# esp_sense.net
KiCad netlist of a schematic drawn in EAGLE
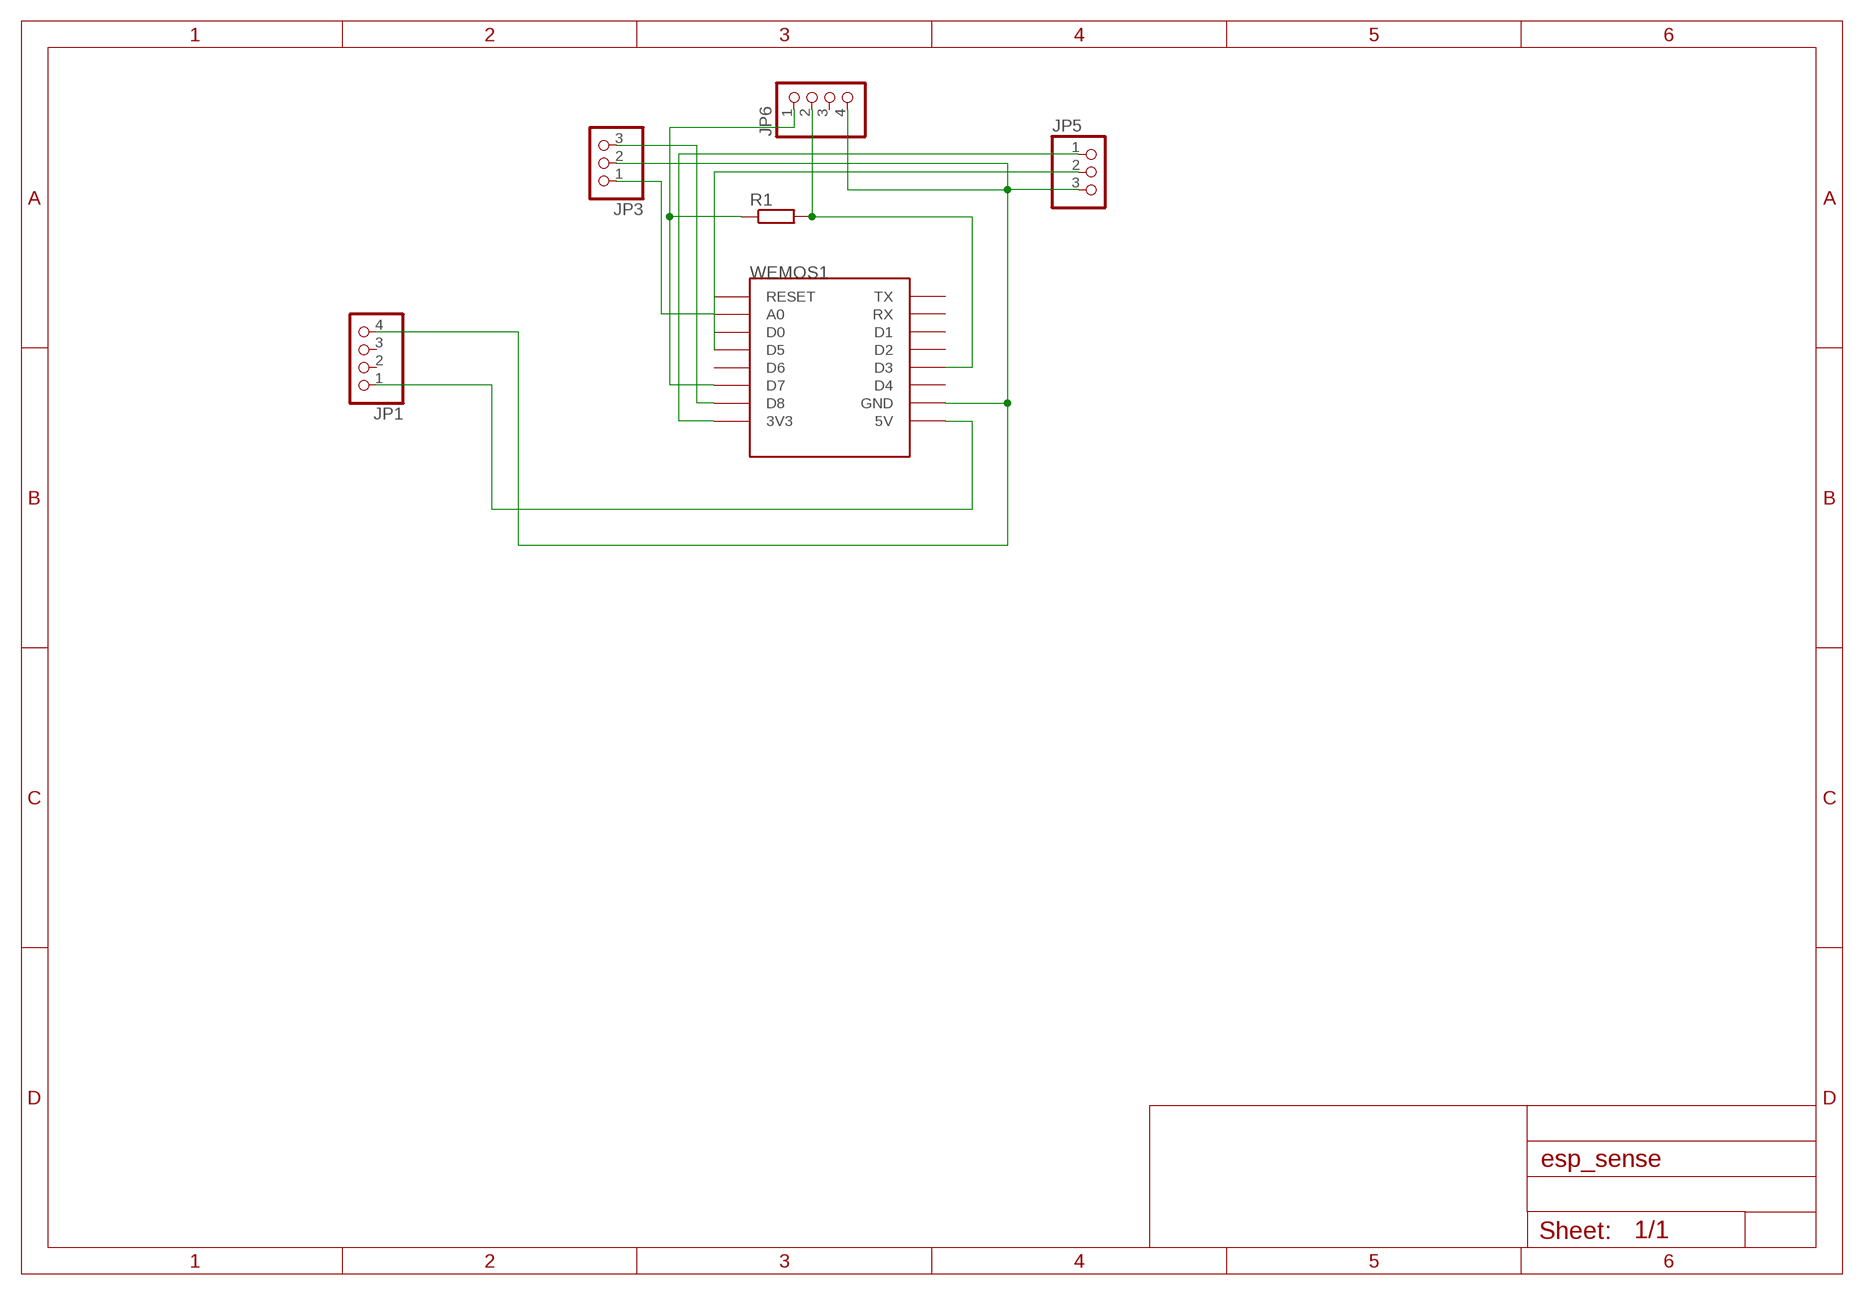
[diagram p0: schematic, sheet 1]

(export (version "E")
  (design (tool "Eeschema 10.0.6"))
  (components
    (comp (ref "JP1")
      (value "PINHD-1X4")
      (footprint "eagle-import:1X04")
      (libsource (lib "eagle-import") (part "PINHD-1X4"))
    )
    (comp (ref "JP3")
      (value "PINHD-1X3")
      (footprint "eagle-import:1X03")
      (libsource (lib "eagle-import") (part "PINHD-1X3"))
    )
    (comp (ref "JP5")
      (value "PINHD-1X3")
      (footprint "eagle-import:1X03")
      (libsource (lib "eagle-import") (part "PINHD-1X3"))
    )
    (comp (ref "JP6")
      (value "PINHD-1X4")
      (footprint "eagle-import:1X04")
      (libsource (lib "eagle-import") (part "PINHD-1X4"))
    )
    (comp (ref "R1")
      (value "R-EU_0207/2V")
      (footprint "eagle-import:0207_2V")
      (libsource (lib "eagle-import") (part "R-EU_0207/2V"))
    )
    (comp (ref "WEMOS1")
      (value "WEMOS-D1-MINI")
      (footprint "eagle-import:WEMOS-D1-MINI")
      (libsource (lib "eagle-import") (part "WEMOS-D1-MINI"))
    )
  )
  (nets
    (net (code "1") (name "Net-(JP1-Pad1)") (class "Default")
      (node (ref "JP1") (pin "1") (pinfunction "1_1") (pintype "passive"))
      (node (ref "WEMOS1") (pin "5V") (pinfunction "5V_5V") (pintype "bidirectional"))
    )
    (net (code "2") (name "Net-(JP1-Pad4)") (class "Default")
      (node (ref "JP1") (pin "4") (pinfunction "4_4") (pintype "passive"))
      (node (ref "JP3") (pin "2") (pinfunction "2_2") (pintype "passive"))
      (node (ref "JP5") (pin "3") (pinfunction "3_3") (pintype "passive"))
      (node (ref "JP6") (pin "4") (pinfunction "4_4") (pintype "passive"))
      (node (ref "WEMOS1") (pin "GND") (pinfunction "GND_GND") (pintype "bidirectional"))
    )
    (net (code "3") (name "Net-(JP3-Pad1)") (class "Default")
      (node (ref "JP3") (pin "1") (pinfunction "1_1") (pintype "passive"))
      (node (ref "WEMOS1") (pin "A0") (pinfunction "A0_A0") (pintype "bidirectional"))
    )
    (net (code "4") (name "Net-(JP3-Pad3)") (class "Default")
      (node (ref "JP3") (pin "3") (pinfunction "3_3") (pintype "passive"))
      (node (ref "WEMOS1") (pin "D8") (pinfunction "D8_D8") (pintype "bidirectional"))
    )
    (net (code "5") (name "Net-(JP5-Pad1)") (class "Default")
      (node (ref "JP5") (pin "1") (pinfunction "1_1") (pintype "passive"))
      (node (ref "WEMOS1") (pin "3V3") (pinfunction "3V3_3V3") (pintype "bidirectional"))
    )
    (net (code "6") (name "Net-(JP5-Pad2)") (class "Default")
      (node (ref "JP5") (pin "2") (pinfunction "2_2") (pintype "passive"))
      (node (ref "WEMOS1") (pin "D5") (pinfunction "D5_D5") (pintype "bidirectional"))
    )
    (net (code "7") (name "Net-(JP6-Pad1)") (class "Default")
      (node (ref "JP6") (pin "1") (pinfunction "1_1") (pintype "passive"))
      (node (ref "R1") (pin "1") (pinfunction "1_1") (pintype "passive"))
      (node (ref "WEMOS1") (pin "D7") (pinfunction "D7_D7") (pintype "bidirectional"))
    )
    (net (code "8") (name "Net-(JP6-Pad2)") (class "Default")
      (node (ref "JP6") (pin "2") (pinfunction "2_2") (pintype "passive"))
      (node (ref "R1") (pin "2") (pinfunction "2_2") (pintype "passive"))
      (node (ref "WEMOS1") (pin "D3") (pinfunction "D3_D3") (pintype "bidirectional"))
    )
    (net (code "9") (name "unconnected-(JP1-Pad2)") (class "Default")
      (node (ref "JP1") (pin "2") (pinfunction "2_2") (pintype "passive"))
    )
    (net (code "10") (name "unconnected-(JP1-Pad3)") (class "Default")
      (node (ref "JP1") (pin "3") (pinfunction "3_3") (pintype "passive"))
    )
    (net (code "11") (name "unconnected-(JP6-Pad3)") (class "Default")
      (node (ref "JP6") (pin "3") (pinfunction "3_3") (pintype "passive"))
    )
    (net (code "12") (name "unconnected-(WEMOS1-PadD0)") (class "Default")
      (node (ref "WEMOS1") (pin "D0") (pinfunction "D0_D0") (pintype "bidirectional"))
    )
    (net (code "13") (name "unconnected-(WEMOS1-PadD1)") (class "Default")
      (node (ref "WEMOS1") (pin "D1") (pinfunction "D1_D1") (pintype "bidirectional"))
    )
    (net (code "14") (name "unconnected-(WEMOS1-PadD2)") (class "Default")
      (node (ref "WEMOS1") (pin "D2") (pinfunction "D2_D2") (pintype "bidirectional"))
    )
    (net (code "15") (name "unconnected-(WEMOS1-PadD4)") (class "Default")
      (node (ref "WEMOS1") (pin "D4") (pinfunction "D4_D4") (pintype "bidirectional"))
    )
    (net (code "16") (name "unconnected-(WEMOS1-PadD6)") (class "Default")
      (node (ref "WEMOS1") (pin "D6") (pinfunction "D6_D6") (pintype "bidirectional"))
    )
    (net (code "17") (name "unconnected-(WEMOS1-PadRESET)") (class "Default")
      (node (ref "WEMOS1") (pin "RESET") (pinfunction "RESET_RESET") (pintype "bidirectional"))
    )
    (net (code "18") (name "unconnected-(WEMOS1-PadRX)") (class "Default")
      (node (ref "WEMOS1") (pin "RX") (pinfunction "RX_RX") (pintype "bidirectional"))
    )
    (net (code "19") (name "unconnected-(WEMOS1-PadTX)") (class "Default")
      (node (ref "WEMOS1") (pin "TX") (pinfunction "TX_TX") (pintype "bidirectional"))
    )
  )
)
